# WAVE_shield.net
KiCad netlist of a schematic drawn in EAGLE
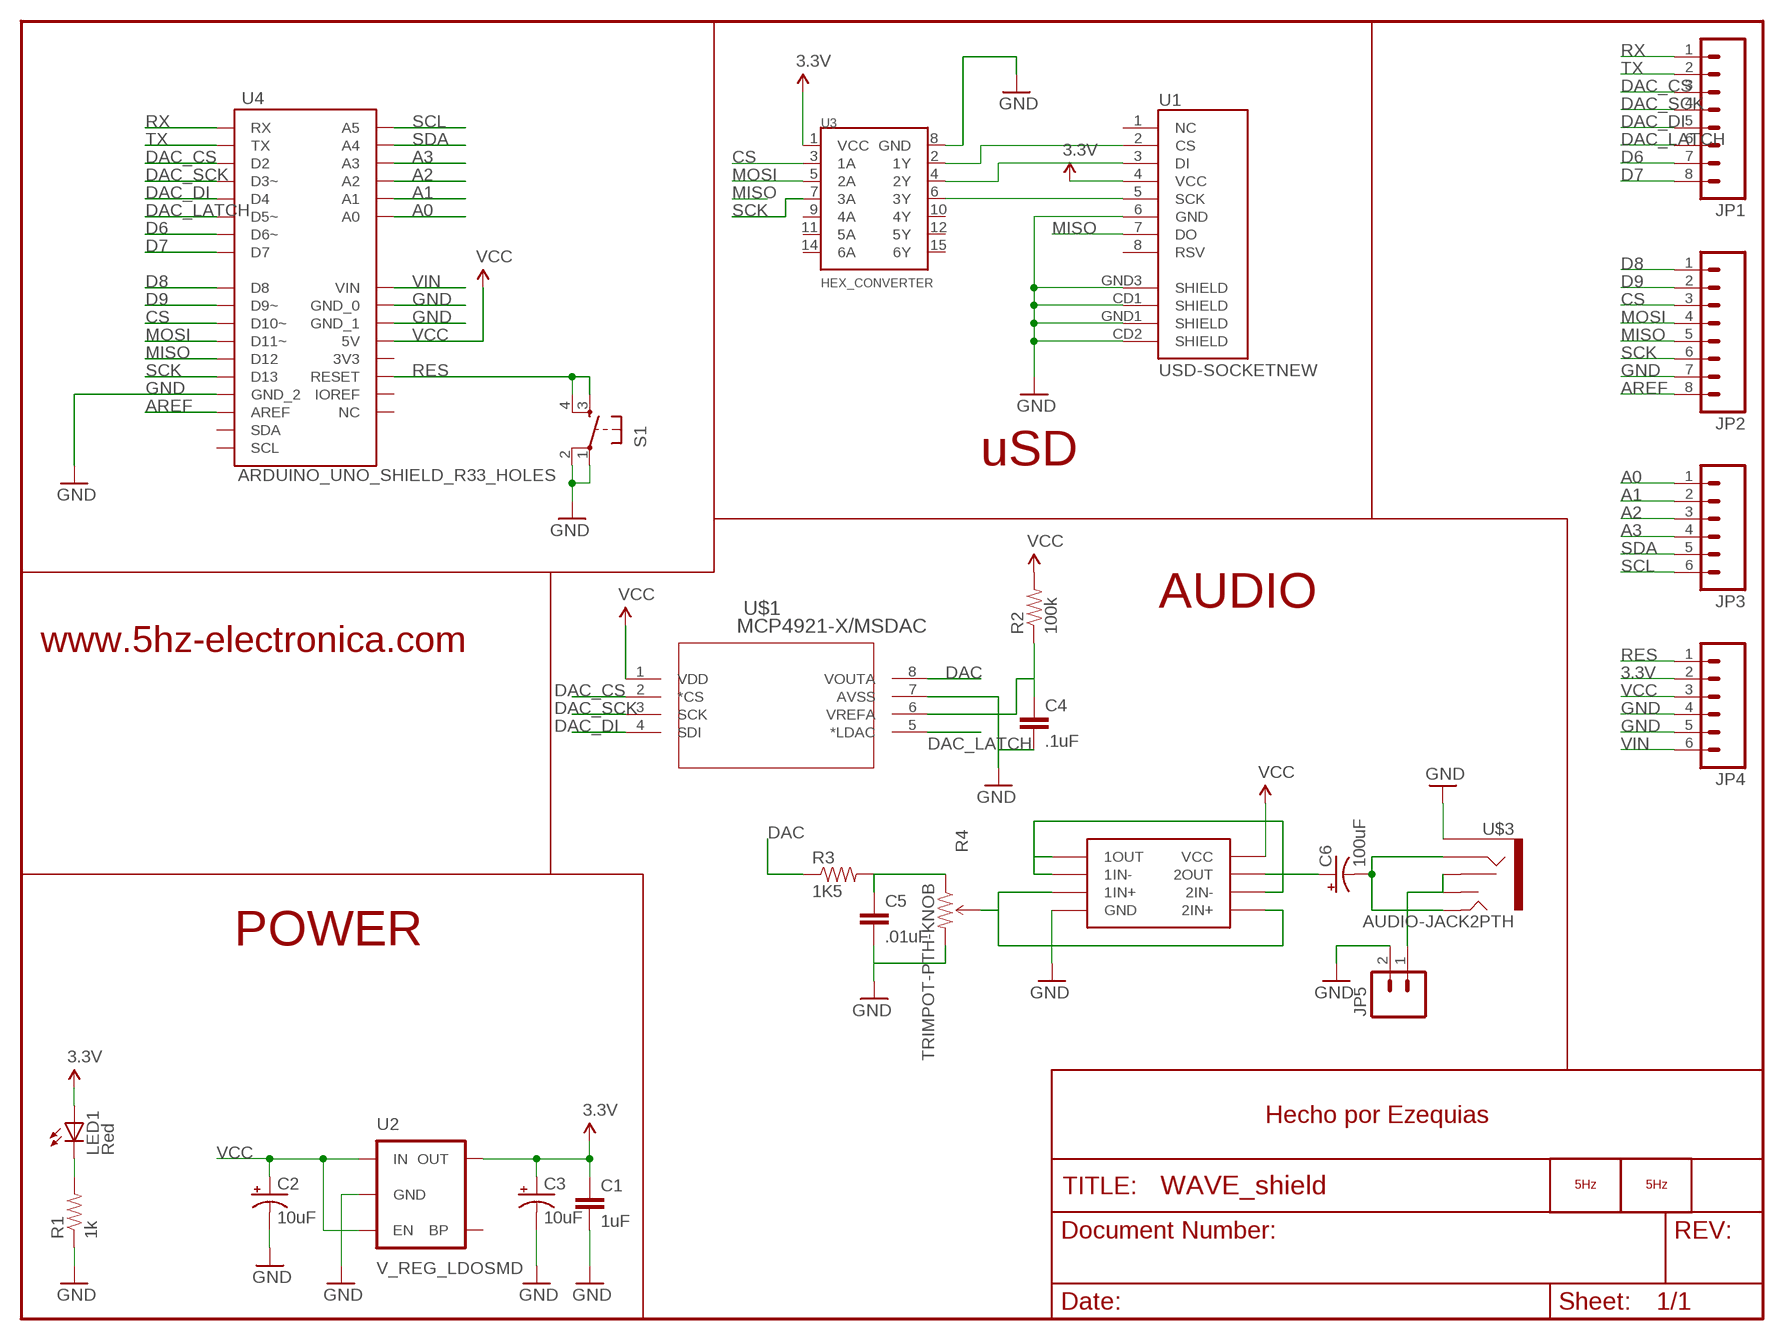
[diagram p0: schematic, sheet 1]

(export (version "E")
  (design (tool "Eeschema 10.0.6"))
  (components
    (comp (ref "C1")
      (value "1uF")
      (footprint "eagle-import:0603-CAP")
      (libsource (lib "eagle-import") (part "CAP0603-CAP"))
    )
    (comp (ref "C2")
      (value "10uF")
      (footprint "eagle-import:EIA3216")
      (libsource (lib "eagle-import") (part "CAP_POL1206"))
    )
    (comp (ref "C3")
      (value "10uF")
      (footprint "eagle-import:EIA3216")
      (libsource (lib "eagle-import") (part "CAP_POL1206"))
    )
    (comp (ref "C4")
      (value ".1uF")
      (footprint "eagle-import:0603-CAP")
      (libsource (lib "eagle-import") (part "CAP0603-CAP"))
    )
    (comp (ref "C5")
      (value ".01uF")
      (footprint "eagle-import:0603-CAP")
      (libsource (lib "eagle-import") (part "CAP0603-CAP"))
    )
    (comp (ref "C6")
      (value "100uF")
      (footprint "eagle-import:EIA3216")
      (libsource (lib "eagle-import") (part "CAP_POL1206"))
    )
    (comp (ref "JP1")
      (value "M08")
      (footprint "eagle-import:1X08")
      (libsource (lib "eagle-import") (part "M08"))
    )
    (comp (ref "JP2")
      (value "M08")
      (footprint "eagle-import:1X08")
      (libsource (lib "eagle-import") (part "M08"))
    )
    (comp (ref "JP3")
      (value "M06SIP")
      (footprint "eagle-import:1X06")
      (libsource (lib "eagle-import") (part "M06SIP"))
    )
    (comp (ref "JP4")
      (value "M06SIP")
      (footprint "eagle-import:1X06")
      (libsource (lib "eagle-import") (part "M06SIP"))
    )
    (comp (ref "JP5")
      (value "M02PTH")
      (footprint "eagle-import:1X02")
      (libsource (lib "eagle-import") (part "M02PTH"))
    )
    (comp (ref "LED1")
      (value "Red")
      (footprint "eagle-import:LED-0603")
      (libsource (lib "eagle-import") (part "LED0603"))
    )
    (comp (ref "LOGO2")
      (value "LOGO_5HZ_MAIN_10MM")
      (footprint "eagle-import:5HZ_LOGO_MAIN_10MM")
      (libsource (lib "eagle-import") (part "LOGO_5HZ_MAIN_10MM"))
    )
    (comp (ref "LOGO3")
      (value "LOGO_5HZ_H_COOPER_15MM")
      (footprint "eagle-import:5HZ_LOGO_H_COOPER_15MM")
      (libsource (lib "eagle-import") (part "LOGO_5HZ_H_COOPER_15MM"))
    )
    (comp (ref "R1")
      (value "1k")
      (footprint "eagle-import:0603-RES")
      (libsource (lib "eagle-import") (part "RESISTOR0603-RES"))
    )
    (comp (ref "R2")
      (value "100k")
      (footprint "eagle-import:0603-RES")
      (libsource (lib "eagle-import") (part "RESISTOR0603-RES"))
    )
    (comp (ref "R3")
      (value "1K5")
      (footprint "eagle-import:0603-RES")
      (libsource (lib "eagle-import") (part "RESISTOR0603-RES"))
    )
    (comp (ref "R4")
      (value "TRIMPOT-PTH-KNOB")
      (footprint "eagle-import:3386U")
      (libsource (lib "eagle-import") (part "TRIMPOT-PTH-KNOB"))
    )
    (comp (ref "S1")
      (value "TAC_SWITCHSMD")
      (footprint "eagle-import:TACTILE_SWITCH_SMD")
      (libsource (lib "eagle-import") (part "TAC_SWITCHSMD"))
    )
    (comp (ref "U$1")
      (value "MCP4921-X/MSDAC")
      (footprint "eagle-import:MSOP8_MC")
      (libsource (lib "eagle-import") (part "MCP4921-X/MSDAC"))
    )
    (comp (ref "U$2")
      (value "LM2904DGKROPAMP")
      (footprint "eagle-import:MSOP8")
      (libsource (lib "eagle-import") (part "LM2904DGKROPAMP"))
    )
    (comp (ref "U$3")
      (value "AUDIO-JACK2PTH")
      (footprint "eagle-import:AUDIO-JACK")
      (libsource (lib "eagle-import") (part "AUDIO-JACK2PTH"))
    )
    (comp (ref "U1")
      (value "USD-SOCKETNEW")
      (footprint "eagle-import:MICRO-SD-SOCKET-PP")
      (libsource (lib "eagle-import") (part "USD-SOCKETNEW"))
    )
    (comp (ref "U2")
      (value "V_REG_LDOSMD")
      (footprint "eagle-import:SOT23-5")
      (libsource (lib "eagle-import") (part "V_REG_LDOSMD"))
    )
    (comp (ref "U3")
      (value "HEX_CONVERTER")
      (footprint "eagle-import:SO016")
      (libsource (lib "eagle-import") (part "HEX_CONVERTER"))
    )
    (comp (ref "U4")
      (value "ARDUINO_UNO_SHIELD_R33_HOLES")
      (footprint "eagle-import:UNO_R3_SHIELD_3_HOLES_NO_SILK")
      (libsource (lib "eagle-import") (part "ARDUINO_UNO_SHIELD_R33_HOLES"))
    )
  )
  (nets
    (net (code "1") (name "/A0") (class "Default")
      (node (ref "JP3") (pin "1") (pinfunction "1_1") (pintype "passive"))
      (node (ref "U4") (pin "A0") (pinfunction "A0_A0") (pintype "bidirectional"))
    )
    (net (code "2") (name "/A1") (class "Default")
      (node (ref "JP3") (pin "2") (pinfunction "2_2") (pintype "passive"))
      (node (ref "U4") (pin "A1") (pinfunction "A1_A1") (pintype "bidirectional"))
    )
    (net (code "3") (name "/A2") (class "Default")
      (node (ref "JP3") (pin "3") (pinfunction "3_3") (pintype "passive"))
      (node (ref "U4") (pin "A2") (pinfunction "A2_A2") (pintype "bidirectional"))
    )
    (net (code "4") (name "/A3") (class "Default")
      (node (ref "JP3") (pin "4") (pinfunction "4_4") (pintype "passive"))
      (node (ref "U4") (pin "A3") (pinfunction "A3_A3") (pintype "bidirectional"))
    )
    (net (code "5") (name "/AREF") (class "Default")
      (node (ref "JP2") (pin "8") (pinfunction "8_8") (pintype "passive"))
      (node (ref "U4") (pin "AREF") (pinfunction "AREF_AREF") (pintype "bidirectional"))
    )
    (net (code "6") (name "/CS") (class "Default")
      (node (ref "JP2") (pin "3") (pinfunction "3_3") (pintype "passive"))
      (node (ref "U3") (pin "3") (pinfunction "1A_3") (pintype "bidirectional"))
      (node (ref "U4") (pin "D10") (pinfunction "D10~{}_D10") (pintype "bidirectional"))
    )
    (net (code "7") (name "/D6") (class "Default")
      (node (ref "JP1") (pin "7") (pinfunction "7_7") (pintype "passive"))
      (node (ref "U4") (pin "D6") (pinfunction "D6~{}_D6") (pintype "bidirectional"))
    )
    (net (code "8") (name "/D7") (class "Default")
      (node (ref "JP1") (pin "8") (pinfunction "8_8") (pintype "passive"))
      (node (ref "U4") (pin "D7") (pinfunction "D7_D7") (pintype "bidirectional"))
    )
    (net (code "9") (name "/D8") (class "Default")
      (node (ref "JP2") (pin "1") (pinfunction "1_1") (pintype "passive"))
      (node (ref "U4") (pin "D8") (pinfunction "D8_D8") (pintype "bidirectional"))
    )
    (net (code "10") (name "/D9") (class "Default")
      (node (ref "JP2") (pin "2") (pinfunction "2_2") (pintype "passive"))
      (node (ref "U4") (pin "D9") (pinfunction "D9~{}_D9") (pintype "bidirectional"))
    )
    (net (code "11") (name "/DAC") (class "Default")
      (node (ref "R3") (pin "1") (pinfunction "1_1") (pintype "passive"))
      (node (ref "U$1") (pin "8") (pinfunction "VOUTA_8") (pintype "passive"))
    )
    (net (code "12") (name "/DAC_CS") (class "Default")
      (node (ref "JP1") (pin "3") (pinfunction "3_3") (pintype "passive"))
      (node (ref "U$1") (pin "2") (pinfunction "*CS_2") (pintype "passive"))
      (node (ref "U4") (pin "D2") (pinfunction "D2_D2") (pintype "bidirectional"))
    )
    (net (code "13") (name "/DAC_DI") (class "Default")
      (node (ref "JP1") (pin "5") (pinfunction "5_5") (pintype "passive"))
      (node (ref "U$1") (pin "4") (pinfunction "SDI_4") (pintype "passive"))
      (node (ref "U4") (pin "D4") (pinfunction "D4_D4") (pintype "bidirectional"))
    )
    (net (code "14") (name "/DAC_LATCH") (class "Default")
      (node (ref "JP1") (pin "6") (pinfunction "6_6") (pintype "passive"))
      (node (ref "U$1") (pin "5") (pinfunction "*LDAC_5") (pintype "passive"))
      (node (ref "U4") (pin "D5") (pinfunction "D5~{}_D5") (pintype "bidirectional"))
    )
    (net (code "15") (name "/DAC_SCK") (class "Default")
      (node (ref "JP1") (pin "4") (pinfunction "4_4") (pintype "passive"))
      (node (ref "U$1") (pin "3") (pinfunction "SCK_3") (pintype "passive"))
      (node (ref "U4") (pin "D3") (pinfunction "D3~{}_D3") (pintype "bidirectional"))
    )
    (net (code "16") (name "/MISO") (class "Default")
      (node (ref "JP2") (pin "5") (pinfunction "5_5") (pintype "passive"))
      (node (ref "U1") (pin "7") (pinfunction "DO_7") (pintype "bidirectional"))
      (node (ref "U4") (pin "D12") (pinfunction "D12_D12") (pintype "bidirectional"))
    )
    (net (code "17") (name "/MOSI") (class "Default")
      (node (ref "JP2") (pin "4") (pinfunction "4_4") (pintype "passive"))
      (node (ref "U3") (pin "5") (pinfunction "2A_5") (pintype "bidirectional"))
      (node (ref "U4") (pin "D11") (pinfunction "D11~{}_D11") (pintype "bidirectional"))
    )
    (net (code "18") (name "/RES") (class "Default")
      (node (ref "JP4") (pin "1") (pinfunction "1_1") (pintype "passive"))
      (node (ref "S1") (pin "3") (pinfunction "3_3") (pintype "passive"))
      (node (ref "S1") (pin "4") (pinfunction "4_4") (pintype "passive"))
      (node (ref "U4") (pin "RES") (pinfunction "RESET_RES") (pintype "bidirectional"))
    )
    (net (code "19") (name "/RX") (class "Default")
      (node (ref "JP1") (pin "1") (pinfunction "1_1") (pintype "passive"))
      (node (ref "U4") (pin "RX") (pinfunction "RX_RX") (pintype "bidirectional"))
    )
    (net (code "20") (name "/SCK") (class "Default")
      (node (ref "JP2") (pin "6") (pinfunction "6_6") (pintype "passive"))
      (node (ref "U3") (pin "7") (pinfunction "3A_7") (pintype "bidirectional"))
      (node (ref "U4") (pin "D13") (pinfunction "D13_D13") (pintype "bidirectional"))
    )
    (net (code "21") (name "/SCL") (class "Default")
      (node (ref "JP3") (pin "6") (pinfunction "6_6") (pintype "passive"))
      (node (ref "U4") (pin "A5") (pinfunction "A5_A5") (pintype "bidirectional"))
    )
    (net (code "22") (name "/SDA") (class "Default")
      (node (ref "JP3") (pin "5") (pinfunction "5_5") (pintype "passive"))
      (node (ref "U4") (pin "A4") (pinfunction "A4_A4") (pintype "bidirectional"))
    )
    (net (code "23") (name "/TX") (class "Default")
      (node (ref "JP1") (pin "2") (pinfunction "2_2") (pintype "passive"))
      (node (ref "U4") (pin "TX") (pinfunction "TX_TX") (pintype "bidirectional"))
    )
    (net (code "24") (name "/VIN") (class "Default")
      (node (ref "JP4") (pin "6") (pinfunction "6_6") (pintype "passive"))
      (node (ref "U4") (pin "VIN") (pinfunction "VIN_VIN") (pintype "bidirectional"))
    )
    (net (code "25") (name "3.3V") (class "Default")
      (node (ref "C1") (pin "1") (pinfunction "1_1") (pintype "passive"))
      (node (ref "C3") (pin "A") (pinfunction "+_A") (pintype "passive"))
      (node (ref "JP4") (pin "2") (pinfunction "2_2") (pintype "passive"))
      (node (ref "LED1") (pin "A") (pinfunction "A_A") (pintype "passive"))
      (node (ref "U1") (pin "4") (pinfunction "VCC_4") (pintype "bidirectional"))
      (node (ref "U2") (pin "5") (pinfunction "OUT_5") (pintype "passive"))
      (node (ref "U3") (pin "1") (pinfunction "VCC_1") (pintype "bidirectional"))
    )
    (net (code "26") (name "GND") (class "Default")
      (node (ref "C1") (pin "2") (pinfunction "2_2") (pintype "passive"))
      (node (ref "C2") (pin "C") (pinfunction "-_C") (pintype "passive"))
      (node (ref "C3") (pin "C") (pinfunction "-_C") (pintype "passive"))
      (node (ref "C4") (pin "2") (pinfunction "2_2") (pintype "passive"))
      (node (ref "C5") (pin "2") (pinfunction "2_2") (pintype "passive"))
      (node (ref "JP2") (pin "7") (pinfunction "7_7") (pintype "passive"))
      (node (ref "JP4") (pin "4") (pinfunction "4_4") (pintype "passive"))
      (node (ref "JP4") (pin "5") (pinfunction "5_5") (pintype "passive"))
      (node (ref "JP5") (pin "2") (pinfunction "2_2") (pintype "passive"))
      (node (ref "R1") (pin "1") (pinfunction "1_1") (pintype "passive"))
      (node (ref "R4") (pin "3") (pinfunction "CW_3") (pintype "passive"))
      (node (ref "S1") (pin "1") (pinfunction "1_1") (pintype "passive"))
      (node (ref "S1") (pin "2") (pinfunction "2_2") (pintype "passive"))
      (node (ref "U$1") (pin "7") (pinfunction "AVSS_7") (pintype "passive"))
      (node (ref "U$2") (pin "4") (pinfunction "GND_4") (pintype "bidirectional"))
      (node (ref "U$3") (pin "SLEEVE") (pinfunction "SLEEVE_SLEEVE") (pintype "bidirectional"))
      (node (ref "U1") (pin "6") (pinfunction "GND_6") (pintype "bidirectional"))
      (node (ref "U1") (pin "CD1") (pinfunction "SHIELD_CD1") (pintype "bidirectional"))
      (node (ref "U1") (pin "CD2") (pinfunction "SHIELD_CD2") (pintype "bidirectional"))
      (node (ref "U1") (pin "GND1") (pinfunction "SHIELD_GND1") (pintype "bidirectional"))
      (node (ref "U1") (pin "GND3") (pinfunction "SHIELD_GND3") (pintype "bidirectional"))
      (node (ref "U2") (pin "2") (pinfunction "GND_2") (pintype "input"))
      (node (ref "U3") (pin "8") (pinfunction "GND_8") (pintype "bidirectional"))
      (node (ref "U4") (pin "GND_0") (pinfunction "GND_0_GND_0") (pintype "bidirectional"))
      (node (ref "U4") (pin "GND_1") (pinfunction "GND_1_GND_1") (pintype "bidirectional"))
      (node (ref "U4") (pin "GND_2") (pinfunction "GND_2_GND_2") (pintype "bidirectional"))
    )
    (net (code "27") (name "Net-(C6-+)") (class "Default")
      (node (ref "C6") (pin "A") (pinfunction "+_A") (pintype "passive"))
      (node (ref "U$2") (pin "1") (pinfunction "1OUT_1") (pintype "bidirectional"))
      (node (ref "U$2") (pin "2") (pinfunction "1IN-_2") (pintype "bidirectional"))
      (node (ref "U$2") (pin "6") (pinfunction "2IN-_6") (pintype "bidirectional"))
      (node (ref "U$2") (pin "7") (pinfunction "2OUT_7") (pintype "bidirectional"))
    )
    (net (code "28") (name "Net-(C6--)") (class "Default")
      (node (ref "C6") (pin "C") (pinfunction "-_C") (pintype "passive"))
      (node (ref "U$3") (pin "RING") (pinfunction "RING_RING") (pintype "bidirectional"))
      (node (ref "U$3") (pin "TIP") (pinfunction "TIP_TIP") (pintype "bidirectional"))
    )
    (net (code "29") (name "Net-(JP5-Pad1)") (class "Default")
      (node (ref "JP5") (pin "1") (pinfunction "1_1") (pintype "passive"))
      (node (ref "U$3") (pin "RSH") (pinfunction "RSH_RSH") (pintype "bidirectional"))
      (node (ref "U$3") (pin "TSH") (pinfunction "TSH_TSH") (pintype "bidirectional"))
    )
    (net (code "30") (name "Net-(LED1-PadC)") (class "Default")
      (node (ref "LED1") (pin "C") (pinfunction "C_C") (pintype "passive"))
      (node (ref "R1") (pin "2") (pinfunction "2_2") (pintype "passive"))
    )
    (net (code "31") (name "Net-(R4-CCW)") (class "Default")
      (node (ref "C5") (pin "1") (pinfunction "1_1") (pintype "passive"))
      (node (ref "R3") (pin "2") (pinfunction "2_2") (pintype "passive"))
      (node (ref "R4") (pin "1") (pinfunction "CCW_1") (pintype "passive"))
    )
    (net (code "32") (name "Net-(R4-WIPER)") (class "Default")
      (node (ref "R4") (pin "2") (pinfunction "WIPER_2") (pintype "passive"))
      (node (ref "U$2") (pin "3") (pinfunction "1IN+_3") (pintype "bidirectional"))
      (node (ref "U$2") (pin "5") (pinfunction "2IN+_5") (pintype "bidirectional"))
    )
    (net (code "33") (name "Net-(U$1-VREFA)") (class "Default")
      (node (ref "C4") (pin "1") (pinfunction "1_1") (pintype "passive"))
      (node (ref "R2") (pin "1") (pinfunction "1_1") (pintype "passive"))
      (node (ref "U$1") (pin "6") (pinfunction "VREFA_6") (pintype "passive"))
    )
    (net (code "34") (name "Net-(U1-CS)") (class "Default")
      (node (ref "U1") (pin "2") (pinfunction "CS_2") (pintype "bidirectional"))
      (node (ref "U3") (pin "2") (pinfunction "1Y_2") (pintype "bidirectional"))
    )
    (net (code "35") (name "Net-(U1-DI)") (class "Default")
      (node (ref "U1") (pin "3") (pinfunction "DI_3") (pintype "bidirectional"))
      (node (ref "U3") (pin "4") (pinfunction "2Y_4") (pintype "bidirectional"))
    )
    (net (code "36") (name "Net-(U1-SCK)") (class "Default")
      (node (ref "U1") (pin "5") (pinfunction "SCK_5") (pintype "bidirectional"))
      (node (ref "U3") (pin "6") (pinfunction "3Y_6") (pintype "bidirectional"))
    )
    (net (code "37") (name "VCC") (class "Default")
      (node (ref "C2") (pin "A") (pinfunction "+_A") (pintype "passive"))
      (node (ref "JP4") (pin "3") (pinfunction "3_3") (pintype "passive"))
      (node (ref "R2") (pin "2") (pinfunction "2_2") (pintype "passive"))
      (node (ref "U$1") (pin "1") (pinfunction "VDD_1") (pintype "passive"))
      (node (ref "U$2") (pin "8") (pinfunction "VCC_8") (pintype "bidirectional"))
      (node (ref "U2") (pin "1") (pinfunction "IN_1") (pintype "input"))
      (node (ref "U2") (pin "3") (pinfunction "EN_3") (pintype "input"))
      (node (ref "U4") (pin "5V") (pinfunction "5V_5V") (pintype "bidirectional"))
    )
    (net (code "38") (name "unconnected-(U1-NC-Pad1)") (class "Default")
      (node (ref "U1") (pin "1") (pinfunction "NC_1") (pintype "bidirectional"))
    )
    (net (code "39") (name "unconnected-(U1-RSV-Pad8)") (class "Default")
      (node (ref "U1") (pin "8") (pinfunction "RSV_8") (pintype "bidirectional"))
    )
    (net (code "40") (name "unconnected-(U2-BP-Pad4)") (class "Default")
      (node (ref "U2") (pin "4") (pinfunction "BP_4") (pintype "input"))
    )
    (net (code "41") (name "unconnected-(U3-4A-Pad9)") (class "Default")
      (node (ref "U3") (pin "9") (pinfunction "4A_9") (pintype "bidirectional"))
    )
    (net (code "42") (name "unconnected-(U3-4Y-Pad10)") (class "Default")
      (node (ref "U3") (pin "10") (pinfunction "4Y_10") (pintype "bidirectional"))
    )
    (net (code "43") (name "unconnected-(U3-5A-Pad11)") (class "Default")
      (node (ref "U3") (pin "11") (pinfunction "5A_11") (pintype "bidirectional"))
    )
    (net (code "44") (name "unconnected-(U3-5Y-Pad12)") (class "Default")
      (node (ref "U3") (pin "12") (pinfunction "5Y_12") (pintype "bidirectional"))
    )
    (net (code "45") (name "unconnected-(U3-6A-Pad14)") (class "Default")
      (node (ref "U3") (pin "14") (pinfunction "6A_14") (pintype "bidirectional"))
    )
    (net (code "46") (name "unconnected-(U3-6Y-Pad15)") (class "Default")
      (node (ref "U3") (pin "15") (pinfunction "6Y_15") (pintype "bidirectional"))
    )
    (net (code "47") (name "unconnected-(U4-3V3-Pad3.3V)") (class "Default")
      (node (ref "U4") (pin "3.3V") (pinfunction "3V3_3.3V") (pintype "bidirectional"))
    )
    (net (code "48") (name "unconnected-(U4-PadIOREF)") (class "Default")
      (node (ref "U4") (pin "IOREF") (pinfunction "IOREF_IOREF") (pintype "bidirectional"))
    )
    (net (code "49") (name "unconnected-(U4-PadNC)") (class "Default")
      (node (ref "U4") (pin "NC") (pinfunction "NC_NC") (pintype "no_connect"))
    )
    (net (code "50") (name "unconnected-(U4-PadSCL)") (class "Default")
      (node (ref "U4") (pin "SCL") (pinfunction "SCL_SCL") (pintype "bidirectional"))
    )
    (net (code "51") (name "unconnected-(U4-PadSDA)") (class "Default")
      (node (ref "U4") (pin "SDA") (pinfunction "SDA_SDA") (pintype "bidirectional"))
    )
  )
)
